# 16LEDsPuzzle.net
KiCad netlist of a schematic drawn in EAGLE
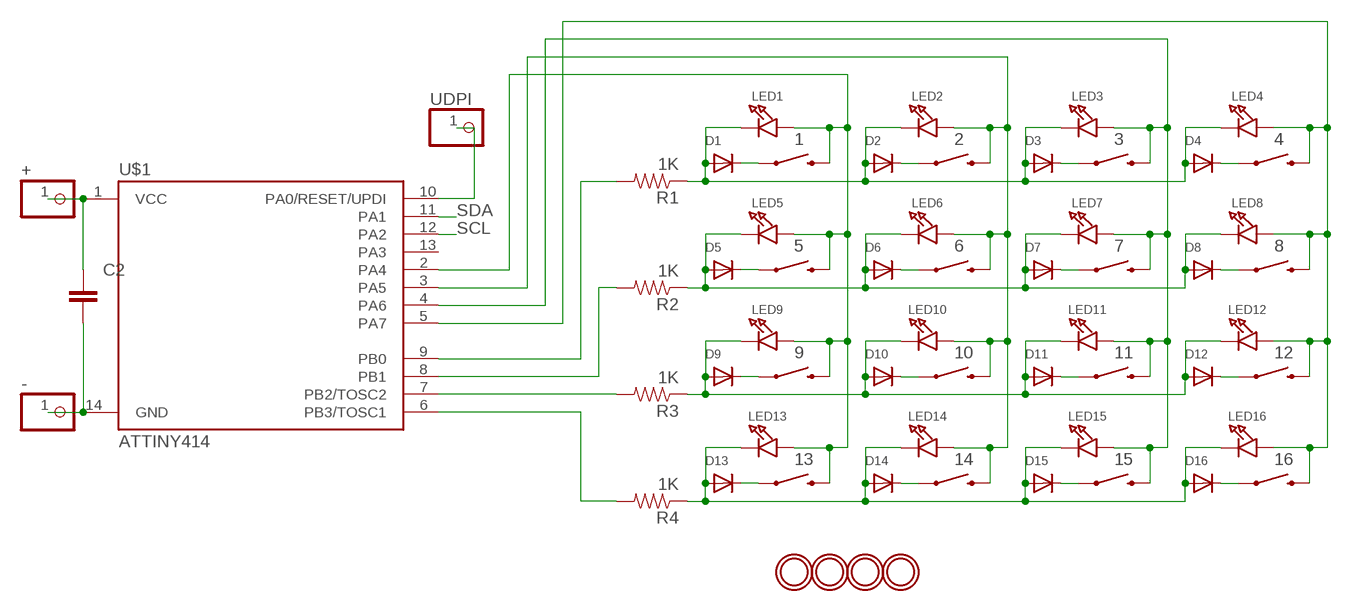
[diagram p0: schematic, sheet 1]

(export (version "E")
  (design (tool "Eeschema 10.0.6"))
  (components
    (comp (ref "+")
      (value "HEADER-1X1ROUND")
      (footprint "eagle-import:1X01_ROUND")
      (libsource (lib "eagle-import") (part "HEADER-1X1ROUND"))
    )
    (comp (ref "-")
      (value "HEADER-1X1ROUND")
      (footprint "eagle-import:1X01_ROUND")
      (libsource (lib "eagle-import") (part "HEADER-1X1ROUND"))
    )
    (comp (ref "1")
      (value "SWITCH-MOMENTARY-2SMD-4")
      (footprint "eagle-import:TACTILE_SWITCH_TALL")
      (libsource (lib "eagle-import") (part "SWITCH-MOMENTARY-2SMD-4"))
    )
    (comp (ref "2")
      (value "SWITCH-MOMENTARY-2SMD-4")
      (footprint "eagle-import:TACTILE_SWITCH_TALL")
      (libsource (lib "eagle-import") (part "SWITCH-MOMENTARY-2SMD-4"))
    )
    (comp (ref "3")
      (value "SWITCH-MOMENTARY-2SMD-4")
      (footprint "eagle-import:TACTILE_SWITCH_TALL")
      (libsource (lib "eagle-import") (part "SWITCH-MOMENTARY-2SMD-4"))
    )
    (comp (ref "4")
      (value "SWITCH-MOMENTARY-2SMD-4")
      (footprint "eagle-import:TACTILE_SWITCH_TALL")
      (libsource (lib "eagle-import") (part "SWITCH-MOMENTARY-2SMD-4"))
    )
    (comp (ref "5")
      (value "SWITCH-MOMENTARY-2SMD-4")
      (footprint "eagle-import:TACTILE_SWITCH_TALL")
      (libsource (lib "eagle-import") (part "SWITCH-MOMENTARY-2SMD-4"))
    )
    (comp (ref "6")
      (value "SWITCH-MOMENTARY-2SMD-4")
      (footprint "eagle-import:TACTILE_SWITCH_TALL")
      (libsource (lib "eagle-import") (part "SWITCH-MOMENTARY-2SMD-4"))
    )
    (comp (ref "7")
      (value "SWITCH-MOMENTARY-2SMD-4")
      (footprint "eagle-import:TACTILE_SWITCH_TALL")
      (libsource (lib "eagle-import") (part "SWITCH-MOMENTARY-2SMD-4"))
    )
    (comp (ref "8")
      (value "SWITCH-MOMENTARY-2SMD-4")
      (footprint "eagle-import:TACTILE_SWITCH_TALL")
      (libsource (lib "eagle-import") (part "SWITCH-MOMENTARY-2SMD-4"))
    )
    (comp (ref "9")
      (value "SWITCH-MOMENTARY-2SMD-4")
      (footprint "eagle-import:TACTILE_SWITCH_TALL")
      (libsource (lib "eagle-import") (part "SWITCH-MOMENTARY-2SMD-4"))
    )
    (comp (ref "10")
      (value "SWITCH-MOMENTARY-2SMD-4")
      (footprint "eagle-import:TACTILE_SWITCH_TALL")
      (libsource (lib "eagle-import") (part "SWITCH-MOMENTARY-2SMD-4"))
    )
    (comp (ref "11")
      (value "SWITCH-MOMENTARY-2SMD-4")
      (footprint "eagle-import:TACTILE_SWITCH_TALL")
      (libsource (lib "eagle-import") (part "SWITCH-MOMENTARY-2SMD-4"))
    )
    (comp (ref "12")
      (value "SWITCH-MOMENTARY-2SMD-4")
      (footprint "eagle-import:TACTILE_SWITCH_TALL")
      (libsource (lib "eagle-import") (part "SWITCH-MOMENTARY-2SMD-4"))
    )
    (comp (ref "13")
      (value "SWITCH-MOMENTARY-2SMD-4")
      (footprint "eagle-import:TACTILE_SWITCH_TALL")
      (libsource (lib "eagle-import") (part "SWITCH-MOMENTARY-2SMD-4"))
    )
    (comp (ref "14")
      (value "SWITCH-MOMENTARY-2SMD-4")
      (footprint "eagle-import:TACTILE_SWITCH_TALL")
      (libsource (lib "eagle-import") (part "SWITCH-MOMENTARY-2SMD-4"))
    )
    (comp (ref "15")
      (value "SWITCH-MOMENTARY-2SMD-4")
      (footprint "eagle-import:TACTILE_SWITCH_TALL")
      (libsource (lib "eagle-import") (part "SWITCH-MOMENTARY-2SMD-4"))
    )
    (comp (ref "16")
      (value "SWITCH-MOMENTARY-2SMD-4")
      (footprint "eagle-import:TACTILE_SWITCH_TALL")
      (libsource (lib "eagle-import") (part "SWITCH-MOMENTARY-2SMD-4"))
    )
    (comp (ref "C2")
      (value "100n")
      (footprint "eagle-import:0805")
      (libsource (lib "eagle-import") (part "CAP0805"))
    )
    (comp (ref "D1")
      (value "DIODESOD-123")
      (footprint "eagle-import:SOD-123")
      (libsource (lib "eagle-import") (part "DIODESOD-123"))
    )
    (comp (ref "D2")
      (value "DIODESOD-123")
      (footprint "eagle-import:SOD-123")
      (libsource (lib "eagle-import") (part "DIODESOD-123"))
    )
    (comp (ref "D3")
      (value "DIODESOD-123")
      (footprint "eagle-import:SOD-123")
      (libsource (lib "eagle-import") (part "DIODESOD-123"))
    )
    (comp (ref "D4")
      (value "DIODESOD-123")
      (footprint "eagle-import:SOD-123")
      (libsource (lib "eagle-import") (part "DIODESOD-123"))
    )
    (comp (ref "D5")
      (value "DIODESOD-123")
      (footprint "eagle-import:SOD-123")
      (libsource (lib "eagle-import") (part "DIODESOD-123"))
    )
    (comp (ref "D6")
      (value "DIODESOD-123")
      (footprint "eagle-import:SOD-123")
      (libsource (lib "eagle-import") (part "DIODESOD-123"))
    )
    (comp (ref "D7")
      (value "DIODESOD-123")
      (footprint "eagle-import:SOD-123")
      (libsource (lib "eagle-import") (part "DIODESOD-123"))
    )
    (comp (ref "D8")
      (value "DIODESOD-123")
      (footprint "eagle-import:SOD-123")
      (libsource (lib "eagle-import") (part "DIODESOD-123"))
    )
    (comp (ref "D9")
      (value "DIODESOD-123")
      (footprint "eagle-import:SOD-123")
      (libsource (lib "eagle-import") (part "DIODESOD-123"))
    )
    (comp (ref "D10")
      (value "DIODESOD-123")
      (footprint "eagle-import:SOD-123")
      (libsource (lib "eagle-import") (part "DIODESOD-123"))
    )
    (comp (ref "D11")
      (value "DIODESOD-123")
      (footprint "eagle-import:SOD-123")
      (libsource (lib "eagle-import") (part "DIODESOD-123"))
    )
    (comp (ref "D12")
      (value "DIODESOD-123")
      (footprint "eagle-import:SOD-123")
      (libsource (lib "eagle-import") (part "DIODESOD-123"))
    )
    (comp (ref "D13")
      (value "DIODESOD-123")
      (footprint "eagle-import:SOD-123")
      (libsource (lib "eagle-import") (part "DIODESOD-123"))
    )
    (comp (ref "D14")
      (value "DIODESOD-123")
      (footprint "eagle-import:SOD-123")
      (libsource (lib "eagle-import") (part "DIODESOD-123"))
    )
    (comp (ref "D15")
      (value "DIODESOD-123")
      (footprint "eagle-import:SOD-123")
      (libsource (lib "eagle-import") (part "DIODESOD-123"))
    )
    (comp (ref "D16")
      (value "DIODESOD-123")
      (footprint "eagle-import:SOD-123")
      (libsource (lib "eagle-import") (part "DIODESOD-123"))
    )
    (comp (ref "LED1")
      (value "GREEN")
      (footprint "eagle-import:CHIPLED_0805_NOOUTLINE")
      (libsource (lib "eagle-import") (part "LED0805_NOOUTLINE"))
    )
    (comp (ref "LED2")
      (value "GREEN")
      (footprint "eagle-import:CHIPLED_0805_NOOUTLINE")
      (libsource (lib "eagle-import") (part "LED0805_NOOUTLINE"))
    )
    (comp (ref "LED3")
      (value "GREEN")
      (footprint "eagle-import:CHIPLED_0805_NOOUTLINE")
      (libsource (lib "eagle-import") (part "LED0805_NOOUTLINE"))
    )
    (comp (ref "LED4")
      (value "GREEN")
      (footprint "eagle-import:CHIPLED_0805_NOOUTLINE")
      (libsource (lib "eagle-import") (part "LED0805_NOOUTLINE"))
    )
    (comp (ref "LED5")
      (value "GREEN")
      (footprint "eagle-import:CHIPLED_0805_NOOUTLINE")
      (libsource (lib "eagle-import") (part "LED0805_NOOUTLINE"))
    )
    (comp (ref "LED6")
      (value "GREEN")
      (footprint "eagle-import:CHIPLED_0805_NOOUTLINE")
      (libsource (lib "eagle-import") (part "LED0805_NOOUTLINE"))
    )
    (comp (ref "LED7")
      (value "GREEN")
      (footprint "eagle-import:CHIPLED_0805_NOOUTLINE")
      (libsource (lib "eagle-import") (part "LED0805_NOOUTLINE"))
    )
    (comp (ref "LED8")
      (value "GREEN")
      (footprint "eagle-import:CHIPLED_0805_NOOUTLINE")
      (libsource (lib "eagle-import") (part "LED0805_NOOUTLINE"))
    )
    (comp (ref "LED9")
      (value "GREEN")
      (footprint "eagle-import:CHIPLED_0805_NOOUTLINE")
      (libsource (lib "eagle-import") (part "LED0805_NOOUTLINE"))
    )
    (comp (ref "LED10")
      (value "GREEN")
      (footprint "eagle-import:CHIPLED_0805_NOOUTLINE")
      (libsource (lib "eagle-import") (part "LED0805_NOOUTLINE"))
    )
    (comp (ref "LED11")
      (value "GREEN")
      (footprint "eagle-import:CHIPLED_0805_NOOUTLINE")
      (libsource (lib "eagle-import") (part "LED0805_NOOUTLINE"))
    )
    (comp (ref "LED12")
      (value "GREEN")
      (footprint "eagle-import:CHIPLED_0805_NOOUTLINE")
      (libsource (lib "eagle-import") (part "LED0805_NOOUTLINE"))
    )
    (comp (ref "LED13")
      (value "GREEN")
      (footprint "eagle-import:CHIPLED_0805_NOOUTLINE")
      (libsource (lib "eagle-import") (part "LED0805_NOOUTLINE"))
    )
    (comp (ref "LED14")
      (value "GREEN")
      (footprint "eagle-import:CHIPLED_0805_NOOUTLINE")
      (libsource (lib "eagle-import") (part "LED0805_NOOUTLINE"))
    )
    (comp (ref "LED15")
      (value "GREEN")
      (footprint "eagle-import:CHIPLED_0805_NOOUTLINE")
      (libsource (lib "eagle-import") (part "LED0805_NOOUTLINE"))
    )
    (comp (ref "LED16")
      (value "GREEN")
      (footprint "eagle-import:CHIPLED_0805_NOOUTLINE")
      (libsource (lib "eagle-import") (part "LED0805_NOOUTLINE"))
    )
    (comp (ref "R1")
      (value "1K")
      (footprint "eagle-import:0805")
      (libsource (lib "eagle-import") (part "RESISTOR0805-RES"))
    )
    (comp (ref "R2")
      (value "1K")
      (footprint "eagle-import:0805")
      (libsource (lib "eagle-import") (part "RESISTOR0805-RES"))
    )
    (comp (ref "R3")
      (value "1K")
      (footprint "eagle-import:0805")
      (libsource (lib "eagle-import") (part "RESISTOR0805-RES"))
    )
    (comp (ref "R4")
      (value "1K")
      (footprint "eagle-import:0805")
      (libsource (lib "eagle-import") (part "RESISTOR0805-RES"))
    )
    (comp (ref "U$1")
      (value "ATTINY414")
      (footprint "eagle-import:SO14")
      (libsource (lib "eagle-import") (part "ATTINY414"))
    )
    (comp (ref "U$2")
      (value "MOUNTINGHOLE2.5")
      (footprint "eagle-import:MOUNTINGHOLE_2.5_PLATED")
      (libsource (lib "eagle-import") (part "MOUNTINGHOLE2.5"))
    )
    (comp (ref "U$3")
      (value "MOUNTINGHOLE2.5")
      (footprint "eagle-import:MOUNTINGHOLE_2.5_PLATED")
      (libsource (lib "eagle-import") (part "MOUNTINGHOLE2.5"))
    )
    (comp (ref "U$4")
      (value "MOUNTINGHOLE2.5")
      (footprint "eagle-import:MOUNTINGHOLE_2.5_PLATED")
      (libsource (lib "eagle-import") (part "MOUNTINGHOLE2.5"))
    )
    (comp (ref "U$5")
      (value "MOUNTINGHOLE2.5")
      (footprint "eagle-import:MOUNTINGHOLE_2.5_PLATED")
      (libsource (lib "eagle-import") (part "MOUNTINGHOLE2.5"))
    )
    (comp (ref "UDPI")
      (value "HEADER-1X1ROUND")
      (footprint "eagle-import:1X01_ROUND")
      (libsource (lib "eagle-import") (part "HEADER-1X1ROUND"))
    )
  )
  (nets
    (net (code "1") (name "/SCL") (class "Default")
      (node (ref "U$1") (pin "12") (pinfunction "PA2_12") (pintype "bidirectional"))
    )
    (net (code "2") (name "/SDA") (class "Default")
      (node (ref "U$1") (pin "11") (pinfunction "PA1_11") (pintype "bidirectional"))
    )
    (net (code "3") (name "Net-(1-1)") (class "Default")
      (node (ref "1") (pin "A2") (pinfunction "1_A2") (pintype "passive"))
      (node (ref "D1") (pin "C") (pinfunction "C_C") (pintype "passive"))
    )
    (net (code "4") (name "Net-(1-2)") (class "Default")
      (node (ref "1") (pin "B2") (pinfunction "2_B2") (pintype "passive"))
      (node (ref "13") (pin "B2") (pinfunction "2_B2") (pintype "passive"))
      (node (ref "5") (pin "B2") (pinfunction "2_B2") (pintype "passive"))
      (node (ref "9") (pin "B2") (pinfunction "2_B2") (pintype "passive"))
      (node (ref "LED1") (pin "A") (pinfunction "A_A") (pintype "passive"))
      (node (ref "LED13") (pin "A") (pinfunction "A_A") (pintype "passive"))
      (node (ref "LED5") (pin "A") (pinfunction "A_A") (pintype "passive"))
      (node (ref "LED9") (pin "A") (pinfunction "A_A") (pintype "passive"))
      (node (ref "U$1") (pin "2") (pinfunction "PA4_2") (pintype "bidirectional"))
    )
    (net (code "5") (name "Net-(2-1)") (class "Default")
      (node (ref "2") (pin "A2") (pinfunction "1_A2") (pintype "passive"))
      (node (ref "D2") (pin "C") (pinfunction "C_C") (pintype "passive"))
    )
    (net (code "6") (name "Net-(3-1)") (class "Default")
      (node (ref "3") (pin "A2") (pinfunction "1_A2") (pintype "passive"))
      (node (ref "D3") (pin "C") (pinfunction "C_C") (pintype "passive"))
    )
    (net (code "7") (name "Net-(4-1)") (class "Default")
      (node (ref "4") (pin "A2") (pinfunction "1_A2") (pintype "passive"))
      (node (ref "D4") (pin "C") (pinfunction "C_C") (pintype "passive"))
    )
    (net (code "8") (name "Net-(5-1)") (class "Default")
      (node (ref "5") (pin "A2") (pinfunction "1_A2") (pintype "passive"))
      (node (ref "D5") (pin "C") (pinfunction "C_C") (pintype "passive"))
    )
    (net (code "9") (name "Net-(6-1)") (class "Default")
      (node (ref "6") (pin "A2") (pinfunction "1_A2") (pintype "passive"))
      (node (ref "D6") (pin "C") (pinfunction "C_C") (pintype "passive"))
    )
    (net (code "10") (name "Net-(7-1)") (class "Default")
      (node (ref "7") (pin "A2") (pinfunction "1_A2") (pintype "passive"))
      (node (ref "D7") (pin "C") (pinfunction "C_C") (pintype "passive"))
    )
    (net (code "11") (name "Net-(8-1)") (class "Default")
      (node (ref "8") (pin "A2") (pinfunction "1_A2") (pintype "passive"))
      (node (ref "D8") (pin "C") (pinfunction "C_C") (pintype "passive"))
    )
    (net (code "12") (name "Net-(9-1)") (class "Default")
      (node (ref "9") (pin "A2") (pinfunction "1_A2") (pintype "passive"))
      (node (ref "D9") (pin "C") (pinfunction "C_C") (pintype "passive"))
    )
    (net (code "13") (name "Net-(10-1)") (class "Default")
      (node (ref "10") (pin "A2") (pinfunction "1_A2") (pintype "passive"))
      (node (ref "D10") (pin "C") (pinfunction "C_C") (pintype "passive"))
    )
    (net (code "14") (name "Net-(10-2)") (class "Default")
      (node (ref "10") (pin "B2") (pinfunction "2_B2") (pintype "passive"))
      (node (ref "14") (pin "B2") (pinfunction "2_B2") (pintype "passive"))
      (node (ref "2") (pin "B2") (pinfunction "2_B2") (pintype "passive"))
      (node (ref "6") (pin "B2") (pinfunction "2_B2") (pintype "passive"))
      (node (ref "LED10") (pin "A") (pinfunction "A_A") (pintype "passive"))
      (node (ref "LED14") (pin "A") (pinfunction "A_A") (pintype "passive"))
      (node (ref "LED2") (pin "A") (pinfunction "A_A") (pintype "passive"))
      (node (ref "LED6") (pin "A") (pinfunction "A_A") (pintype "passive"))
      (node (ref "U$1") (pin "3") (pinfunction "PA5_3") (pintype "bidirectional"))
    )
    (net (code "15") (name "Net-(11-1)") (class "Default")
      (node (ref "11") (pin "A2") (pinfunction "1_A2") (pintype "passive"))
      (node (ref "D11") (pin "C") (pinfunction "C_C") (pintype "passive"))
    )
    (net (code "16") (name "Net-(11-2)") (class "Default")
      (node (ref "11") (pin "B2") (pinfunction "2_B2") (pintype "passive"))
      (node (ref "15") (pin "B2") (pinfunction "2_B2") (pintype "passive"))
      (node (ref "3") (pin "B2") (pinfunction "2_B2") (pintype "passive"))
      (node (ref "7") (pin "B2") (pinfunction "2_B2") (pintype "passive"))
      (node (ref "LED11") (pin "A") (pinfunction "A_A") (pintype "passive"))
      (node (ref "LED15") (pin "A") (pinfunction "A_A") (pintype "passive"))
      (node (ref "LED3") (pin "A") (pinfunction "A_A") (pintype "passive"))
      (node (ref "LED7") (pin "A") (pinfunction "A_A") (pintype "passive"))
      (node (ref "U$1") (pin "4") (pinfunction "PA6_4") (pintype "bidirectional"))
    )
    (net (code "17") (name "Net-(12-1)") (class "Default")
      (node (ref "12") (pin "A2") (pinfunction "1_A2") (pintype "passive"))
      (node (ref "D12") (pin "C") (pinfunction "C_C") (pintype "passive"))
    )
    (net (code "18") (name "Net-(12-2)") (class "Default")
      (node (ref "12") (pin "B2") (pinfunction "2_B2") (pintype "passive"))
      (node (ref "16") (pin "B2") (pinfunction "2_B2") (pintype "passive"))
      (node (ref "4") (pin "B2") (pinfunction "2_B2") (pintype "passive"))
      (node (ref "8") (pin "B2") (pinfunction "2_B2") (pintype "passive"))
      (node (ref "LED12") (pin "A") (pinfunction "A_A") (pintype "passive"))
      (node (ref "LED16") (pin "A") (pinfunction "A_A") (pintype "passive"))
      (node (ref "LED4") (pin "A") (pinfunction "A_A") (pintype "passive"))
      (node (ref "LED8") (pin "A") (pinfunction "A_A") (pintype "passive"))
      (node (ref "U$1") (pin "5") (pinfunction "PA7_5") (pintype "bidirectional"))
    )
    (net (code "19") (name "Net-(13-1)") (class "Default")
      (node (ref "13") (pin "A2") (pinfunction "1_A2") (pintype "passive"))
      (node (ref "D13") (pin "C") (pinfunction "C_C") (pintype "passive"))
    )
    (net (code "20") (name "Net-(14-1)") (class "Default")
      (node (ref "14") (pin "A2") (pinfunction "1_A2") (pintype "passive"))
      (node (ref "D14") (pin "C") (pinfunction "C_C") (pintype "passive"))
    )
    (net (code "21") (name "Net-(15-1)") (class "Default")
      (node (ref "15") (pin "A2") (pinfunction "1_A2") (pintype "passive"))
      (node (ref "D15") (pin "C") (pinfunction "C_C") (pintype "passive"))
    )
    (net (code "22") (name "Net-(16-1)") (class "Default")
      (node (ref "16") (pin "A2") (pinfunction "1_A2") (pintype "passive"))
      (node (ref "D16") (pin "C") (pinfunction "C_C") (pintype "passive"))
    )
    (net (code "23") (name "Net-(D1-PadA)") (class "Default")
      (node (ref "D1") (pin "A") (pinfunction "A_A") (pintype "passive"))
      (node (ref "D2") (pin "A") (pinfunction "A_A") (pintype "passive"))
      (node (ref "D3") (pin "A") (pinfunction "A_A") (pintype "passive"))
      (node (ref "D4") (pin "A") (pinfunction "A_A") (pintype "passive"))
      (node (ref "LED1") (pin "C") (pinfunction "C_C") (pintype "passive"))
      (node (ref "LED2") (pin "C") (pinfunction "C_C") (pintype "passive"))
      (node (ref "LED3") (pin "C") (pinfunction "C_C") (pintype "passive"))
      (node (ref "LED4") (pin "C") (pinfunction "C_C") (pintype "passive"))
      (node (ref "R1") (pin "1") (pinfunction "1_1") (pintype "passive"))
    )
    (net (code "24") (name "Net-(D5-PadA)") (class "Default")
      (node (ref "D5") (pin "A") (pinfunction "A_A") (pintype "passive"))
      (node (ref "D6") (pin "A") (pinfunction "A_A") (pintype "passive"))
      (node (ref "D7") (pin "A") (pinfunction "A_A") (pintype "passive"))
      (node (ref "D8") (pin "A") (pinfunction "A_A") (pintype "passive"))
      (node (ref "LED5") (pin "C") (pinfunction "C_C") (pintype "passive"))
      (node (ref "LED6") (pin "C") (pinfunction "C_C") (pintype "passive"))
      (node (ref "LED7") (pin "C") (pinfunction "C_C") (pintype "passive"))
      (node (ref "LED8") (pin "C") (pinfunction "C_C") (pintype "passive"))
      (node (ref "R2") (pin "1") (pinfunction "1_1") (pintype "passive"))
    )
    (net (code "25") (name "Net-(D10-PadA)") (class "Default")
      (node (ref "D10") (pin "A") (pinfunction "A_A") (pintype "passive"))
      (node (ref "D11") (pin "A") (pinfunction "A_A") (pintype "passive"))
      (node (ref "D12") (pin "A") (pinfunction "A_A") (pintype "passive"))
      (node (ref "D9") (pin "A") (pinfunction "A_A") (pintype "passive"))
      (node (ref "LED10") (pin "C") (pinfunction "C_C") (pintype "passive"))
      (node (ref "LED11") (pin "C") (pinfunction "C_C") (pintype "passive"))
      (node (ref "LED12") (pin "C") (pinfunction "C_C") (pintype "passive"))
      (node (ref "LED9") (pin "C") (pinfunction "C_C") (pintype "passive"))
      (node (ref "R3") (pin "1") (pinfunction "1_1") (pintype "passive"))
    )
    (net (code "26") (name "Net-(D13-PadA)") (class "Default")
      (node (ref "D13") (pin "A") (pinfunction "A_A") (pintype "passive"))
      (node (ref "D14") (pin "A") (pinfunction "A_A") (pintype "passive"))
      (node (ref "D15") (pin "A") (pinfunction "A_A") (pintype "passive"))
      (node (ref "D16") (pin "A") (pinfunction "A_A") (pintype "passive"))
      (node (ref "LED13") (pin "C") (pinfunction "C_C") (pintype "passive"))
      (node (ref "LED14") (pin "C") (pinfunction "C_C") (pintype "passive"))
      (node (ref "LED15") (pin "C") (pinfunction "C_C") (pintype "passive"))
      (node (ref "LED16") (pin "C") (pinfunction "C_C") (pintype "passive"))
      (node (ref "R4") (pin "1") (pinfunction "1_1") (pintype "passive"))
    )
    (net (code "27") (name "Net-(U$1-GND)") (class "Default")
      (node (ref "-") (pin "1") (pinfunction "1_1") (pintype "passive"))
      (node (ref "C2") (pin "2") (pinfunction "2_2") (pintype "passive"))
      (node (ref "U$1") (pin "14") (pinfunction "GND_14") (pintype "bidirectional"))
    )
    (net (code "28") (name "Net-(U$1-PA0{slash}RESET{slash}UPDI)") (class "Default")
      (node (ref "U$1") (pin "10") (pinfunction "PA0/RESET/UPDI_10") (pintype "bidirectional"))
      (node (ref "UDPI") (pin "1") (pinfunction "1_1") (pintype "passive"))
    )
    (net (code "29") (name "Net-(U$1-PB0)") (class "Default")
      (node (ref "R1") (pin "2") (pinfunction "2_2") (pintype "passive"))
      (node (ref "U$1") (pin "9") (pinfunction "PB0_9") (pintype "bidirectional"))
    )
    (net (code "30") (name "Net-(U$1-PB1)") (class "Default")
      (node (ref "R2") (pin "2") (pinfunction "2_2") (pintype "passive"))
      (node (ref "U$1") (pin "8") (pinfunction "PB1_8") (pintype "bidirectional"))
    )
    (net (code "31") (name "Net-(U$1-PB2{slash}TOSC2)") (class "Default")
      (node (ref "R3") (pin "2") (pinfunction "2_2") (pintype "passive"))
      (node (ref "U$1") (pin "7") (pinfunction "PB2/TOSC2_7") (pintype "bidirectional"))
    )
    (net (code "32") (name "Net-(U$1-PB3{slash}TOSC1)") (class "Default")
      (node (ref "R4") (pin "2") (pinfunction "2_2") (pintype "passive"))
      (node (ref "U$1") (pin "6") (pinfunction "PB3/TOSC1_6") (pintype "bidirectional"))
    )
    (net (code "33") (name "Net-(U$1-VCC)") (class "Default")
      (node (ref "+") (pin "1") (pinfunction "1_1") (pintype "passive"))
      (node (ref "C2") (pin "1") (pinfunction "1_1") (pintype "passive"))
      (node (ref "U$1") (pin "1") (pinfunction "VCC_1") (pintype "bidirectional"))
    )
    (net (code "34") (name "unconnected-(U$1-PA3-Pad13)") (class "Default")
      (node (ref "U$1") (pin "13") (pinfunction "PA3_13") (pintype "bidirectional"))
    )
  )
)
